# Clock.net
KiCad netlist of a schematic drawn in Altium Designer
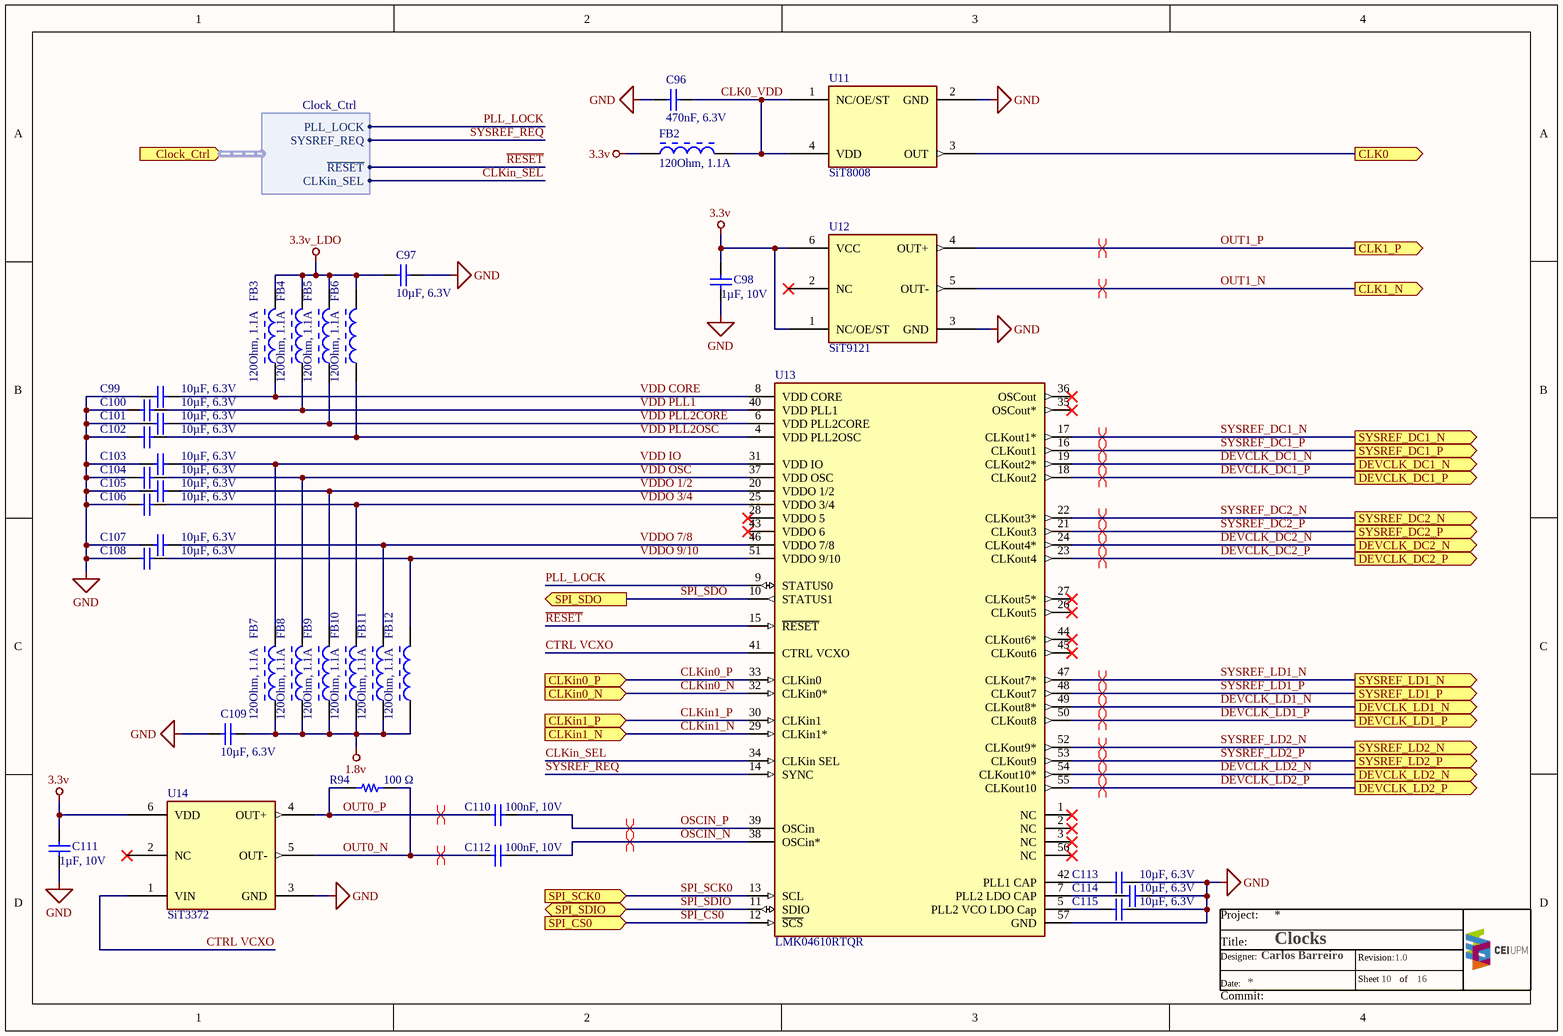
[diagram p0: Clock.SchDoc]

(export (version "E")
  (design (tool "Eeschema 10.0.6"))
  (components
    (comp (ref "C96")
      (value "470nF, 6.3V")
      (footprint "WURTH_WCAP-CSGP_0402")
      (description "WCAP-CSGP Multilayer Ceramic Chip Capacitor, General Purpose, size 0402, X5R, 470nF, 6.3V")
      (fields
        (field (name "MANUFACTURER PART NUMBER") "885012105004")
        (field (name "MANUFACTURER") "Wurth Elektronik")
      )
      (libsource (lib "SpaceVNXBaseBoard") (part "885012105004"))
    )
    (comp (ref "C97")
      (value "10µF, 6.3V")
      (footprint "WURTH_WCAP-CSGP_0402")
      (description "WCAP-CSGP Multilayer Ceramic Chip Capacitor, General Purpose, size 0402, X5R, 10uF, 6.3V")
      (fields
        (field (name "MANUFACTURER PART NUMBER") "885012105020")
        (field (name "MANUFACTURER") "Wurth Elektronik")
      )
      (libsource (lib "SpaceVNXBaseBoard") (part "885012105020"))
    )
    (comp (ref "C98")
      (value "1µF, 10V")
      (footprint "WURTH_WCAP-CSGP_0402")
      (description "WCAP-CSGP Multilayer Ceramic Chip Capacitor, General Purpose, size 0402, X5R, 1uF, 10V")
      (fields
        (field (name "MANUFACTURER PART NUMBER") "885012105012")
        (field (name "MANUFACTURER") "Wurth Elektronik")
      )
      (libsource (lib "SpaceVNXBaseBoard") (part "885012105012"))
    )
    (comp (ref "C99")
      (value "10µF, 6.3V")
      (footprint "WURTH_WCAP-CSGP_0402")
      (description "WCAP-CSGP Multilayer Ceramic Chip Capacitor, General Purpose, size 0402, X5R, 10uF, 6.3V")
      (fields
        (field (name "MANUFACTURER PART NUMBER") "885012105020")
        (field (name "MANUFACTURER") "Wurth Elektronik")
      )
      (libsource (lib "SpaceVNXBaseBoard") (part "885012105020"))
    )
    (comp (ref "C100")
      (value "10µF, 6.3V")
      (footprint "WURTH_WCAP-CSGP_0402")
      (description "WCAP-CSGP Multilayer Ceramic Chip Capacitor, General Purpose, size 0402, X5R, 10uF, 6.3V")
      (fields
        (field (name "MANUFACTURER PART NUMBER") "885012105020")
        (field (name "MANUFACTURER") "Wurth Elektronik")
      )
      (libsource (lib "SpaceVNXBaseBoard") (part "885012105020"))
    )
    (comp (ref "C101")
      (value "10µF, 6.3V")
      (footprint "WURTH_WCAP-CSGP_0402")
      (description "WCAP-CSGP Multilayer Ceramic Chip Capacitor, General Purpose, size 0402, X5R, 10uF, 6.3V")
      (fields
        (field (name "MANUFACTURER PART NUMBER") "885012105020")
        (field (name "MANUFACTURER") "Wurth Elektronik")
      )
      (libsource (lib "SpaceVNXBaseBoard") (part "885012105020"))
    )
    (comp (ref "C102")
      (value "10µF, 6.3V")
      (footprint "WURTH_WCAP-CSGP_0402")
      (description "WCAP-CSGP Multilayer Ceramic Chip Capacitor, General Purpose, size 0402, X5R, 10uF, 6.3V")
      (fields
        (field (name "MANUFACTURER PART NUMBER") "885012105020")
        (field (name "MANUFACTURER") "Wurth Elektronik")
      )
      (libsource (lib "SpaceVNXBaseBoard") (part "885012105020"))
    )
    (comp (ref "C103")
      (value "10µF, 6.3V")
      (footprint "WURTH_WCAP-CSGP_0402")
      (description "WCAP-CSGP Multilayer Ceramic Chip Capacitor, General Purpose, size 0402, X5R, 10uF, 6.3V")
      (fields
        (field (name "MANUFACTURER PART NUMBER") "885012105020")
        (field (name "MANUFACTURER") "Wurth Elektronik")
      )
      (libsource (lib "SpaceVNXBaseBoard") (part "885012105020"))
    )
    (comp (ref "C104")
      (value "10µF, 6.3V")
      (footprint "WURTH_WCAP-CSGP_0402")
      (description "WCAP-CSGP Multilayer Ceramic Chip Capacitor, General Purpose, size 0402, X5R, 10uF, 6.3V")
      (fields
        (field (name "MANUFACTURER PART NUMBER") "885012105020")
        (field (name "MANUFACTURER") "Wurth Elektronik")
      )
      (libsource (lib "SpaceVNXBaseBoard") (part "885012105020"))
    )
    (comp (ref "C105")
      (value "10µF, 6.3V")
      (footprint "WURTH_WCAP-CSGP_0402")
      (description "WCAP-CSGP Multilayer Ceramic Chip Capacitor, General Purpose, size 0402, X5R, 10uF, 6.3V")
      (fields
        (field (name "MANUFACTURER PART NUMBER") "885012105020")
        (field (name "MANUFACTURER") "Wurth Elektronik")
      )
      (libsource (lib "SpaceVNXBaseBoard") (part "885012105020"))
    )
    (comp (ref "C106")
      (value "10µF, 6.3V")
      (footprint "WURTH_WCAP-CSGP_0402")
      (description "WCAP-CSGP Multilayer Ceramic Chip Capacitor, General Purpose, size 0402, X5R, 10uF, 6.3V")
      (fields
        (field (name "MANUFACTURER PART NUMBER") "885012105020")
        (field (name "MANUFACTURER") "Wurth Elektronik")
      )
      (libsource (lib "SpaceVNXBaseBoard") (part "885012105020"))
    )
    (comp (ref "C107")
      (value "10µF, 6.3V")
      (footprint "WURTH_WCAP-CSGP_0402")
      (description "WCAP-CSGP Multilayer Ceramic Chip Capacitor, General Purpose, size 0402, X5R, 10uF, 6.3V")
      (fields
        (field (name "MANUFACTURER PART NUMBER") "885012105020")
        (field (name "MANUFACTURER") "Wurth Elektronik")
      )
      (libsource (lib "SpaceVNXBaseBoard") (part "885012105020"))
    )
    (comp (ref "C108")
      (value "10µF, 6.3V")
      (footprint "WURTH_WCAP-CSGP_0402")
      (description "WCAP-CSGP Multilayer Ceramic Chip Capacitor, General Purpose, size 0402, X5R, 10uF, 6.3V")
      (fields
        (field (name "MANUFACTURER PART NUMBER") "885012105020")
        (field (name "MANUFACTURER") "Wurth Elektronik")
      )
      (libsource (lib "SpaceVNXBaseBoard") (part "885012105020"))
    )
    (comp (ref "C109")
      (value "10µF, 6.3V")
      (footprint "WURTH_WCAP-CSGP_0402")
      (description "WCAP-CSGP Multilayer Ceramic Chip Capacitor, General Purpose, size 0402, X5R, 10uF, 6.3V")
      (fields
        (field (name "MANUFACTURER PART NUMBER") "885012105020")
        (field (name "MANUFACTURER") "Wurth Elektronik")
      )
      (libsource (lib "SpaceVNXBaseBoard") (part "885012105020"))
    )
    (comp (ref "C110")
      (value "100nF, 10V")
      (footprint "WURTH_WCAP-CSGP_0402")
      (description "WCAP-CSGP Multilayer Ceramic Chip Capacitor, General Purpose, size 0402, X7R, 100nF, 10V")
      (fields
        (field (name "MANUFACTURER PART NUMBER") "885012205018")
        (field (name "MANUFACTURER") "Wurth Elektronik")
      )
      (libsource (lib "SpaceVNXBaseBoard") (part "885012205018"))
    )
    (comp (ref "C111")
      (value "1µF, 10V")
      (footprint "WURTH_WCAP-CSGP_0402")
      (description "WCAP-CSGP Multilayer Ceramic Chip Capacitor, General Purpose, size 0402, X5R, 1uF, 10V")
      (fields
        (field (name "MANUFACTURER PART NUMBER") "885012105012")
        (field (name "MANUFACTURER") "Wurth Elektronik")
      )
      (libsource (lib "SpaceVNXBaseBoard") (part "885012105012"))
    )
    (comp (ref "C112")
      (value "100nF, 10V")
      (footprint "WURTH_WCAP-CSGP_0402")
      (description "WCAP-CSGP Multilayer Ceramic Chip Capacitor, General Purpose, size 0402, X7R, 100nF, 10V")
      (fields
        (field (name "MANUFACTURER PART NUMBER") "885012205018")
        (field (name "MANUFACTURER") "Wurth Elektronik")
      )
      (libsource (lib "SpaceVNXBaseBoard") (part "885012205018"))
    )
    (comp (ref "C113")
      (value "10µF, 6.3V")
      (footprint "WURTH_WCAP-CSGP_0402")
      (description "WCAP-CSGP Multilayer Ceramic Chip Capacitor, General Purpose, size 0402, X5R, 10uF, 6.3V")
      (fields
        (field (name "MANUFACTURER PART NUMBER") "885012105020")
        (field (name "MANUFACTURER") "Wurth Elektronik")
      )
      (libsource (lib "SpaceVNXBaseBoard") (part "885012105020"))
    )
    (comp (ref "C114")
      (value "10µF, 6.3V")
      (footprint "WURTH_WCAP-CSGP_0402")
      (description "WCAP-CSGP Multilayer Ceramic Chip Capacitor, General Purpose, size 0402, X5R, 10uF, 6.3V")
      (fields
        (field (name "MANUFACTURER PART NUMBER") "885012105020")
        (field (name "MANUFACTURER") "Wurth Elektronik")
      )
      (libsource (lib "SpaceVNXBaseBoard") (part "885012105020"))
    )
    (comp (ref "C115")
      (value "10µF, 6.3V")
      (footprint "WURTH_WCAP-CSGP_0402")
      (description "WCAP-CSGP Multilayer Ceramic Chip Capacitor, General Purpose, size 0402, X5R, 10uF, 6.3V")
      (fields
        (field (name "MANUFACTURER PART NUMBER") "885012105020")
        (field (name "MANUFACTURER") "Wurth Elektronik")
      )
      (libsource (lib "SpaceVNXBaseBoard") (part "885012105020"))
    )
    (comp (ref "FB2")
      (value "120Ohm, 1.1A")
      (footprint "WURTH-CBF_0402")
      (description "WE-CBF SMT EMI Suppression Ferrite Bead, size 0402, 120Ohm, 1.1A")
      (fields
        (field (name "MANUFACTURER PART NUMBER") "74279271")
        (field (name "MANUFACTURER") "Wurth Elektronik")
      )
      (libsource (lib "SpaceVNXBaseBoard") (part "74279271"))
    )
    (comp (ref "FB3")
      (value "120Ohm, 1.1A")
      (footprint "WURTH-CBF_0402")
      (description "WE-CBF SMT EMI Suppression Ferrite Bead, size 0402, 120Ohm, 1.1A")
      (fields
        (field (name "MANUFACTURER PART NUMBER") "74279271")
        (field (name "MANUFACTURER") "Wurth Elektronik")
      )
      (libsource (lib "SpaceVNXBaseBoard") (part "74279271"))
    )
    (comp (ref "FB4")
      (value "120Ohm, 1.1A")
      (footprint "WURTH-CBF_0402")
      (description "WE-CBF SMT EMI Suppression Ferrite Bead, size 0402, 120Ohm, 1.1A")
      (fields
        (field (name "MANUFACTURER PART NUMBER") "74279271")
        (field (name "MANUFACTURER") "Wurth Elektronik")
      )
      (libsource (lib "SpaceVNXBaseBoard") (part "74279271"))
    )
    (comp (ref "FB5")
      (value "120Ohm, 1.1A")
      (footprint "WURTH-CBF_0402")
      (description "WE-CBF SMT EMI Suppression Ferrite Bead, size 0402, 120Ohm, 1.1A")
      (fields
        (field (name "MANUFACTURER PART NUMBER") "74279271")
        (field (name "MANUFACTURER") "Wurth Elektronik")
      )
      (libsource (lib "SpaceVNXBaseBoard") (part "74279271"))
    )
    (comp (ref "FB6")
      (value "120Ohm, 1.1A")
      (footprint "WURTH-CBF_0402")
      (description "WE-CBF SMT EMI Suppression Ferrite Bead, size 0402, 120Ohm, 1.1A")
      (fields
        (field (name "MANUFACTURER PART NUMBER") "74279271")
        (field (name "MANUFACTURER") "Wurth Elektronik")
      )
      (libsource (lib "SpaceVNXBaseBoard") (part "74279271"))
    )
    (comp (ref "FB7")
      (value "120Ohm, 1.1A")
      (footprint "WURTH-CBF_0402")
      (description "WE-CBF SMT EMI Suppression Ferrite Bead, size 0402, 120Ohm, 1.1A")
      (fields
        (field (name "MANUFACTURER PART NUMBER") "74279271")
        (field (name "MANUFACTURER") "Wurth Elektronik")
      )
      (libsource (lib "SpaceVNXBaseBoard") (part "74279271"))
    )
    (comp (ref "FB8")
      (value "120Ohm, 1.1A")
      (footprint "WURTH-CBF_0402")
      (description "WE-CBF SMT EMI Suppression Ferrite Bead, size 0402, 120Ohm, 1.1A")
      (fields
        (field (name "MANUFACTURER PART NUMBER") "74279271")
        (field (name "MANUFACTURER") "Wurth Elektronik")
      )
      (libsource (lib "SpaceVNXBaseBoard") (part "74279271"))
    )
    (comp (ref "FB9")
      (value "120Ohm, 1.1A")
      (footprint "WURTH-CBF_0402")
      (description "WE-CBF SMT EMI Suppression Ferrite Bead, size 0402, 120Ohm, 1.1A")
      (fields
        (field (name "MANUFACTURER PART NUMBER") "74279271")
        (field (name "MANUFACTURER") "Wurth Elektronik")
      )
      (libsource (lib "SpaceVNXBaseBoard") (part "74279271"))
    )
    (comp (ref "FB10")
      (value "120Ohm, 1.1A")
      (footprint "WURTH-CBF_0402")
      (description "WE-CBF SMT EMI Suppression Ferrite Bead, size 0402, 120Ohm, 1.1A")
      (fields
        (field (name "MANUFACTURER PART NUMBER") "74279271")
        (field (name "MANUFACTURER") "Wurth Elektronik")
      )
      (libsource (lib "SpaceVNXBaseBoard") (part "74279271"))
    )
    (comp (ref "FB11")
      (value "120Ohm, 1.1A")
      (footprint "WURTH-CBF_0402")
      (description "WE-CBF SMT EMI Suppression Ferrite Bead, size 0402, 120Ohm, 1.1A")
      (fields
        (field (name "MANUFACTURER PART NUMBER") "74279271")
        (field (name "MANUFACTURER") "Wurth Elektronik")
      )
      (libsource (lib "SpaceVNXBaseBoard") (part "74279271"))
    )
    (comp (ref "FB12")
      (value "120Ohm, 1.1A")
      (footprint "WURTH-CBF_0402")
      (description "WE-CBF SMT EMI Suppression Ferrite Bead, size 0402, 120Ohm, 1.1A")
      (fields
        (field (name "MANUFACTURER PART NUMBER") "74279271")
        (field (name "MANUFACTURER") "Wurth Elektronik")
      )
      (libsource (lib "SpaceVNXBaseBoard") (part "74279271"))
    )
    (comp (ref "R94")
      (value "100 Ω")
      (footprint "PANASONIC_ERJ2G_0402")
      (description "General Purpose Thick Film Chip Resistors")
      (fields (field (name "MANUFACTURER") "Panasonic"))
      (libsource (lib "SpaceVNXBaseBoard") (part "ERJ2GEJ101X"))
    )
    (comp (ref "U11")
      (value "SiT8008")
      (footprint "SiTime_5032_4")
      (libsource (lib "SpaceVNXBaseBoard") (part "SiT8008"))
    )
    (comp (ref "U12")
      (value "SiT9121")
      (footprint "SiTime_5032_6")
      (description "Programmable differential oscillator that supports LVPECL and LVDS output.")
      (libsource (lib "SpaceVNXBaseBoard") (part "SiT9121"))
    )
    (comp (ref "U13")
      (value "LMK04610RTQR")
      (footprint "TEXAS_VQFN56")
      (description "Ultra low-noise and low power JESD204B compliant clock jitter cleaner with dual PLLs.")
      (libsource (lib "SpaceVNXBaseBoard") (part "LMK04610RTQR"))
    )
    (comp (ref "U14")
      (value "SiT3372")
      (footprint "SiTime_5032_6")
      (description "Ultra-low Jitter Differential VCXO.")
      (libsource (lib "SpaceVNXBaseBoard") (part "SiT3372"))
    )
  )
  (nets
    (net (code "2") (name "/CLK0") (class "Default")
      (node (ref "U11") (pin "3") (pinfunction "OUT_3") (pintype "output"))
    )
    (net (code "3") (name "/CLK0_VDD") (class "Default")
      (node (ref "C96") (pin "2") (pinfunction "2_2") (pintype "passive"))
      (node (ref "FB2") (pin "1") (pinfunction "1_1") (pintype "passive"))
      (node (ref "U11") (pin "1") (pinfunction "NC/OE/ST_1") (pintype "passive"))
      (node (ref "U11") (pin "4") (pinfunction "VDD_4") (pintype "passive"))
    )
    (net (code "4") (name "/CLKin0_N") (class "Default")
      (node (ref "U13") (pin "32") (pinfunction "CLKin0*_32") (pintype "input"))
    )
    (net (code "5") (name "/CLKin0_P") (class "Default")
      (node (ref "U13") (pin "33") (pinfunction "CLKin0_33") (pintype "input"))
    )
    (net (code "6") (name "/CLKin1_N") (class "Default")
      (node (ref "U13") (pin "29") (pinfunction "CLKin1*_29") (pintype "input"))
    )
    (net (code "7") (name "/CLKin1_P") (class "Default")
      (node (ref "U13") (pin "30") (pinfunction "CLKin1_30") (pintype "input"))
    )
    (net (code "8") (name "/CLKin_SEL") (class "Default")
      (node (ref "U13") (pin "34") (pinfunction "CLKin_SEL_34") (pintype "input"))
    )
    (net (code "9") (name "/CTRL VCXO") (class "Default")
      (node (ref "U13") (pin "41") (pinfunction "CTRL_VCXO_41") (pintype "power_in"))
      (node (ref "U14") (pin "1") (pinfunction "VIN_1") (pintype "passive"))
    )
    (net (code "10") (name "/DEVCLK_DC1_N") (class "Default")
      (node (ref "U13") (pin "19") (pinfunction "CLKout2*_19") (pintype "output"))
    )
    (net (code "11") (name "/DEVCLK_DC1_P") (class "Default")
      (node (ref "U13") (pin "18") (pinfunction "CLKout2_18") (pintype "output"))
    )
    (net (code "12") (name "/DEVCLK_DC2_N") (class "Default")
      (node (ref "U13") (pin "24") (pinfunction "CLKout4*_24") (pintype "output"))
    )
    (net (code "13") (name "/DEVCLK_DC2_P") (class "Default")
      (node (ref "U13") (pin "23") (pinfunction "CLKout4_23") (pintype "output"))
    )
    (net (code "14") (name "/DEVCLK_LD1_N") (class "Default")
      (node (ref "U13") (pin "49") (pinfunction "CLKout8*_49") (pintype "output"))
    )
    (net (code "15") (name "/DEVCLK_LD1_P") (class "Default")
      (node (ref "U13") (pin "50") (pinfunction "CLKout8_50") (pintype "output"))
    )
    (net (code "16") (name "/DEVCLK_LD2_N") (class "Default")
      (node (ref "U13") (pin "54") (pinfunction "CLKout10*_54") (pintype "output"))
    )
    (net (code "17") (name "/DEVCLK_LD2_P") (class "Default")
      (node (ref "U13") (pin "55") (pinfunction "CLKout10_55") (pintype "output"))
    )
    (net (code "18") (name "/OSCIN_N") (class "Default")
      (node (ref "C112") (pin "2") (pinfunction "2_2") (pintype "passive"))
      (node (ref "U13") (pin "38") (pinfunction "OSCin*_38") (pintype "passive"))
    )
    (net (code "19") (name "/OSCIN_P") (class "Default")
      (node (ref "C110") (pin "2") (pinfunction "2_2") (pintype "passive"))
      (node (ref "U13") (pin "39") (pinfunction "OSCin_39") (pintype "passive"))
    )
    (net (code "20") (name "/OUT0_N") (class "Default")
      (node (ref "C112") (pin "1") (pinfunction "1_1") (pintype "passive"))
      (node (ref "R94") (pin "2") (pinfunction "2_2") (pintype "passive"))
      (node (ref "U14") (pin "5") (pinfunction "OUT-_5") (pintype "output"))
    )
    (net (code "21") (name "/OUT0_P") (class "Default")
      (node (ref "C110") (pin "1") (pinfunction "1_1") (pintype "passive"))
      (node (ref "R94") (pin "1") (pinfunction "1_1") (pintype "passive"))
      (node (ref "U14") (pin "4") (pinfunction "OUT+_4") (pintype "output"))
    )
    (net (code "22") (name "/OUT1_N") (class "Default")
      (node (ref "U12") (pin "5") (pinfunction "OUT-_5") (pintype "output"))
    )
    (net (code "23") (name "/OUT1_P") (class "Default")
      (node (ref "U12") (pin "4") (pinfunction "OUT+_4") (pintype "output"))
    )
    (net (code "24") (name "/PLL_LOCK") (class "Default")
      (node (ref "U13") (pin "9") (pinfunction "STATUS0_9") (pintype "bidirectional"))
    )
    (net (code "25") (name "/SPI_CS0") (class "Default")
      (node (ref "U13") (pin "12") (pinfunction "~{SCS}_12") (pintype "input"))
    )
    (net (code "26") (name "/SPI_SCK0") (class "Default")
      (node (ref "U13") (pin "13") (pinfunction "SCL_13") (pintype "input"))
    )
    (net (code "27") (name "/SPI_SDIO") (class "Default")
      (node (ref "U13") (pin "11") (pinfunction "SDIO_11") (pintype "bidirectional"))
    )
    (net (code "28") (name "/SPI_SDO") (class "Default")
      (node (ref "U13") (pin "10") (pinfunction "STATUS1_10") (pintype "output"))
    )
    (net (code "29") (name "/SYSREF_DC1_N") (class "Default")
      (node (ref "U13") (pin "17") (pinfunction "CLKout1*_17") (pintype "output"))
    )
    (net (code "30") (name "/SYSREF_DC1_P") (class "Default")
      (node (ref "U13") (pin "16") (pinfunction "CLKout1_16") (pintype "output"))
    )
    (net (code "31") (name "/SYSREF_DC2_N") (class "Default")
      (node (ref "U13") (pin "22") (pinfunction "CLKout3*_22") (pintype "output"))
    )
    (net (code "32") (name "/SYSREF_DC2_P") (class "Default")
      (node (ref "U13") (pin "21") (pinfunction "CLKout3_21") (pintype "output"))
    )
    (net (code "33") (name "/SYSREF_LD1_N") (class "Default")
      (node (ref "U13") (pin "47") (pinfunction "CLKout7*_47") (pintype "output"))
    )
    (net (code "34") (name "/SYSREF_LD1_P") (class "Default")
      (node (ref "U13") (pin "48") (pinfunction "CLKout7_48") (pintype "output"))
    )
    (net (code "35") (name "/SYSREF_LD2_N") (class "Default")
      (node (ref "U13") (pin "52") (pinfunction "CLKout9*_52") (pintype "output"))
    )
    (net (code "36") (name "/SYSREF_LD2_P") (class "Default")
      (node (ref "U13") (pin "53") (pinfunction "CLKout9_53") (pintype "output"))
    )
    (net (code "37") (name "/SYSREF_REQ") (class "Default")
      (node (ref "U13") (pin "14") (pinfunction "SYNC_14") (pintype "input"))
    )
    (net (code "38") (name "/VDD CORE") (class "Default")
      (node (ref "C99") (pin "2") (pinfunction "2_2") (pintype "passive"))
      (node (ref "FB3") (pin "2") (pinfunction "2_2") (pintype "passive"))
      (node (ref "U13") (pin "8") (pinfunction "VDD_CORE_8") (pintype "power_in"))
    )
    (net (code "39") (name "/VDD IO") (class "Default")
      (node (ref "C103") (pin "2") (pinfunction "2_2") (pintype "passive"))
      (node (ref "FB7") (pin "1") (pinfunction "1_1") (pintype "passive"))
      (node (ref "U13") (pin "31") (pinfunction "VDD_IO_31") (pintype "power_in"))
    )
    (net (code "40") (name "/VDD OSC") (class "Default")
      (node (ref "C104") (pin "2") (pinfunction "2_2") (pintype "passive"))
      (node (ref "FB8") (pin "1") (pinfunction "1_1") (pintype "passive"))
      (node (ref "U13") (pin "37") (pinfunction "VDD_OSC_37") (pintype "power_in"))
    )
    (net (code "41") (name "/VDD PLL1") (class "Default")
      (node (ref "C100") (pin "2") (pinfunction "2_2") (pintype "passive"))
      (node (ref "FB4") (pin "2") (pinfunction "2_2") (pintype "passive"))
      (node (ref "U13") (pin "40") (pinfunction "VDD_PLL1_40") (pintype "power_in"))
    )
    (net (code "42") (name "/VDD PLL2CORE") (class "Default")
      (node (ref "C101") (pin "2") (pinfunction "2_2") (pintype "passive"))
      (node (ref "FB5") (pin "2") (pinfunction "2_2") (pintype "passive"))
      (node (ref "U13") (pin "6") (pinfunction "VDD_PLL2CORE_6") (pintype "power_in"))
    )
    (net (code "43") (name "/VDD PLL2OSC") (class "Default")
      (node (ref "C102") (pin "2") (pinfunction "2_2") (pintype "passive"))
      (node (ref "FB6") (pin "2") (pinfunction "2_2") (pintype "passive"))
      (node (ref "U13") (pin "4") (pinfunction "VDD_PLL2OSC_4") (pintype "power_in"))
    )
    (net (code "44") (name "/VDDO 1{slash}2") (class "Default")
      (node (ref "C105") (pin "2") (pinfunction "2_2") (pintype "passive"))
      (node (ref "FB9") (pin "1") (pinfunction "1_1") (pintype "passive"))
      (node (ref "U13") (pin "20") (pinfunction "VDDO_1/2_20") (pintype "power_in"))
    )
    (net (code "45") (name "/VDDO 3{slash}4") (class "Default")
      (node (ref "C106") (pin "2") (pinfunction "2_2") (pintype "passive"))
      (node (ref "FB10") (pin "1") (pinfunction "1_1") (pintype "passive"))
      (node (ref "U13") (pin "25") (pinfunction "VDDO_3/4_25") (pintype "power_in"))
    )
    (net (code "46") (name "/VDDO 7{slash}8") (class "Default")
      (node (ref "C107") (pin "2") (pinfunction "2_2") (pintype "passive"))
      (node (ref "FB11") (pin "1") (pinfunction "1_1") (pintype "passive"))
      (node (ref "U13") (pin "46") (pinfunction "VDDO_7/8_46") (pintype "power_in"))
    )
    (net (code "47") (name "/VDDO 9{slash}10") (class "Default")
      (node (ref "C108") (pin "2") (pinfunction "2_2") (pintype "passive"))
      (node (ref "FB12") (pin "1") (pinfunction "1_1") (pintype "passive"))
      (node (ref "U13") (pin "51") (pinfunction "VDDO_9/10_51") (pintype "power_in"))
    )
    (net (code "49") (name "/~{RESET}") (class "Default")
      (node (ref "U13") (pin "15") (pinfunction "~{RESET}_15") (pintype "input"))
    )
    (net (code "50") (name "1.8v") (class "Default")
      (node (ref "C109") (pin "2") (pinfunction "2_2") (pintype "passive"))
      (node (ref "FB10") (pin "2") (pinfunction "2_2") (pintype "passive"))
      (node (ref "FB11") (pin "2") (pinfunction "2_2") (pintype "passive"))
      (node (ref "FB12") (pin "2") (pinfunction "2_2") (pintype "passive"))
      (node (ref "FB7") (pin "2") (pinfunction "2_2") (pintype "passive"))
      (node (ref "FB8") (pin "2") (pinfunction "2_2") (pintype "passive"))
      (node (ref "FB9") (pin "2") (pinfunction "2_2") (pintype "passive"))
    )
    (net (code "51") (name "3.3v") (class "Default")
      (node (ref "C111") (pin "2") (pinfunction "2_2") (pintype "passive"))
      (node (ref "C98") (pin "2") (pinfunction "2_2") (pintype "passive"))
      (node (ref "FB2") (pin "2") (pinfunction "2_2") (pintype "passive"))
      (node (ref "U12") (pin "1") (pinfunction "NC/OE/ST_1") (pintype "passive"))
      (node (ref "U12") (pin "6") (pinfunction "VCC_6") (pintype "passive"))
      (node (ref "U14") (pin "6") (pinfunction "VDD_6") (pintype "passive"))
    )
    (net (code "52") (name "3.3v_LDO") (class "Default")
      (node (ref "C97") (pin "1") (pinfunction "1_1") (pintype "passive"))
      (node (ref "FB3") (pin "1") (pinfunction "1_1") (pintype "passive"))
      (node (ref "FB4") (pin "1") (pinfunction "1_1") (pintype "passive"))
      (node (ref "FB5") (pin "1") (pinfunction "1_1") (pintype "passive"))
      (node (ref "FB6") (pin "1") (pinfunction "1_1") (pintype "passive"))
    )
    (net (code "53") (name "GND") (class "Default")
      (node (ref "C100") (pin "1") (pinfunction "1_1") (pintype "passive"))
      (node (ref "C101") (pin "1") (pinfunction "1_1") (pintype "passive"))
      (node (ref "C102") (pin "1") (pinfunction "1_1") (pintype "passive"))
      (node (ref "C103") (pin "1") (pinfunction "1_1") (pintype "passive"))
      (node (ref "C104") (pin "1") (pinfunction "1_1") (pintype "passive"))
      (node (ref "C105") (pin "1") (pinfunction "1_1") (pintype "passive"))
      (node (ref "C106") (pin "1") (pinfunction "1_1") (pintype "passive"))
      (node (ref "C107") (pin "1") (pinfunction "1_1") (pintype "passive"))
      (node (ref "C108") (pin "1") (pinfunction "1_1") (pintype "passive"))
      (node (ref "C109") (pin "1") (pinfunction "1_1") (pintype "passive"))
      (node (ref "C111") (pin "1") (pinfunction "1_1") (pintype "passive"))
      (node (ref "C113") (pin "2") (pinfunction "2_2") (pintype "passive"))
      (node (ref "C114") (pin "2") (pinfunction "2_2") (pintype "passive"))
      (node (ref "C115") (pin "2") (pinfunction "2_2") (pintype "passive"))
      (node (ref "C96") (pin "1") (pinfunction "1_1") (pintype "passive"))
      (node (ref "C97") (pin "2") (pinfunction "2_2") (pintype "passive"))
      (node (ref "C98") (pin "1") (pinfunction "1_1") (pintype "passive"))
      (node (ref "C99") (pin "1") (pinfunction "1_1") (pintype "passive"))
      (node (ref "U11") (pin "2") (pinfunction "GND_2") (pintype "passive"))
      (node (ref "U12") (pin "3") (pinfunction "GND_3") (pintype "passive"))
      (node (ref "U13") (pin "57") (pinfunction "GND_57") (pintype "power_in"))
      (node (ref "U14") (pin "3") (pinfunction "GND_3") (pintype "passive"))
    )
    (net (code "54") (name "Net-(U13-PLL1_CAP)") (class "Default")
      (node (ref "C113") (pin "1") (pinfunction "1_1") (pintype "passive"))
      (node (ref "U13") (pin "42") (pinfunction "PLL1_CAP_42") (pintype "passive"))
    )
    (net (code "55") (name "Net-(U13-PLL2_LDO_CAP)") (class "Default")
      (node (ref "C114") (pin "1") (pinfunction "1_1") (pintype "passive"))
      (node (ref "U13") (pin "7") (pinfunction "PLL2_LDO_CAP_7") (pintype "power_in"))
    )
    (net (code "56") (name "Net-(U13-PLL2_VCO_LDO_Cap)") (class "Default")
      (node (ref "C115") (pin "1") (pinfunction "1_1") (pintype "passive"))
      (node (ref "U13") (pin "5") (pinfunction "PLL2_VCO_LDO_Cap_5") (pintype "power_in"))
    )
    (net (code "57") (name "unconnected-(U12-NC-Pad2)") (class "Default")
      (node (ref "U12") (pin "2") (pinfunction "NC_2") (pintype "passive+no_connect"))
    )
    (net (code "58") (name "unconnected-(U13-CLKout5*-Pad27)") (class "Default")
      (node (ref "U13") (pin "27") (pinfunction "CLKout5*_27") (pintype "output+no_connect"))
    )
    (net (code "59") (name "unconnected-(U13-CLKout5-Pad26)") (class "Default")
      (node (ref "U13") (pin "26") (pinfunction "CLKout5_26") (pintype "output+no_connect"))
    )
    (net (code "60") (name "unconnected-(U13-CLKout6*-Pad44)") (class "Default")
      (node (ref "U13") (pin "44") (pinfunction "CLKout6*_44") (pintype "output+no_connect"))
    )
    (net (code "61") (name "unconnected-(U13-CLKout6-Pad45)") (class "Default")
      (node (ref "U13") (pin "45") (pinfunction "CLKout6_45") (pintype "output+no_connect"))
    )
    (net (code "62") (name "unconnected-(U13-NC-Pad1)") (class "Default")
      (node (ref "U13") (pin "1") (pinfunction "NC_1") (pintype "passive+no_connect"))
    )
    (net (code "63") (name "unconnected-(U13-NC-Pad2)") (class "Default")
      (node (ref "U13") (pin "2") (pinfunction "NC_2") (pintype "passive+no_connect"))
    )
    (net (code "64") (name "unconnected-(U13-NC-Pad3)") (class "Default")
      (node (ref "U13") (pin "3") (pinfunction "NC_3") (pintype "passive+no_connect"))
    )
    (net (code "65") (name "unconnected-(U13-NC-Pad56)") (class "Default")
      (node (ref "U13") (pin "56") (pinfunction "NC_56") (pintype "passive+no_connect"))
    )
    (net (code "66") (name "unconnected-(U13-OSCout*-Pad35)") (class "Default")
      (node (ref "U13") (pin "35") (pinfunction "OSCout*_35") (pintype "output+no_connect"))
    )
    (net (code "67") (name "unconnected-(U13-OSCout-Pad36)") (class "Default")
      (node (ref "U13") (pin "36") (pinfunction "OSCout_36") (pintype "output+no_connect"))
    )
    (net (code "68") (name "unconnected-(U13-VDDO_5-Pad28)") (class "Default")
      (node (ref "U13") (pin "28") (pinfunction "VDDO_5_28") (pintype "power_in+no_connect"))
    )
    (net (code "69") (name "unconnected-(U13-VDDO_6-Pad43)") (class "Default")
      (node (ref "U13") (pin "43") (pinfunction "VDDO_6_43") (pintype "power_in+no_connect"))
    )
    (net (code "70") (name "unconnected-(U14-NC-Pad2)") (class "Default")
      (node (ref "U14") (pin "2") (pinfunction "NC_2") (pintype "passive+no_connect"))
    )
  )
)
